# Prosthesis_Motor_Shield.net
KiCad netlist of a schematic drawn in EAGLE
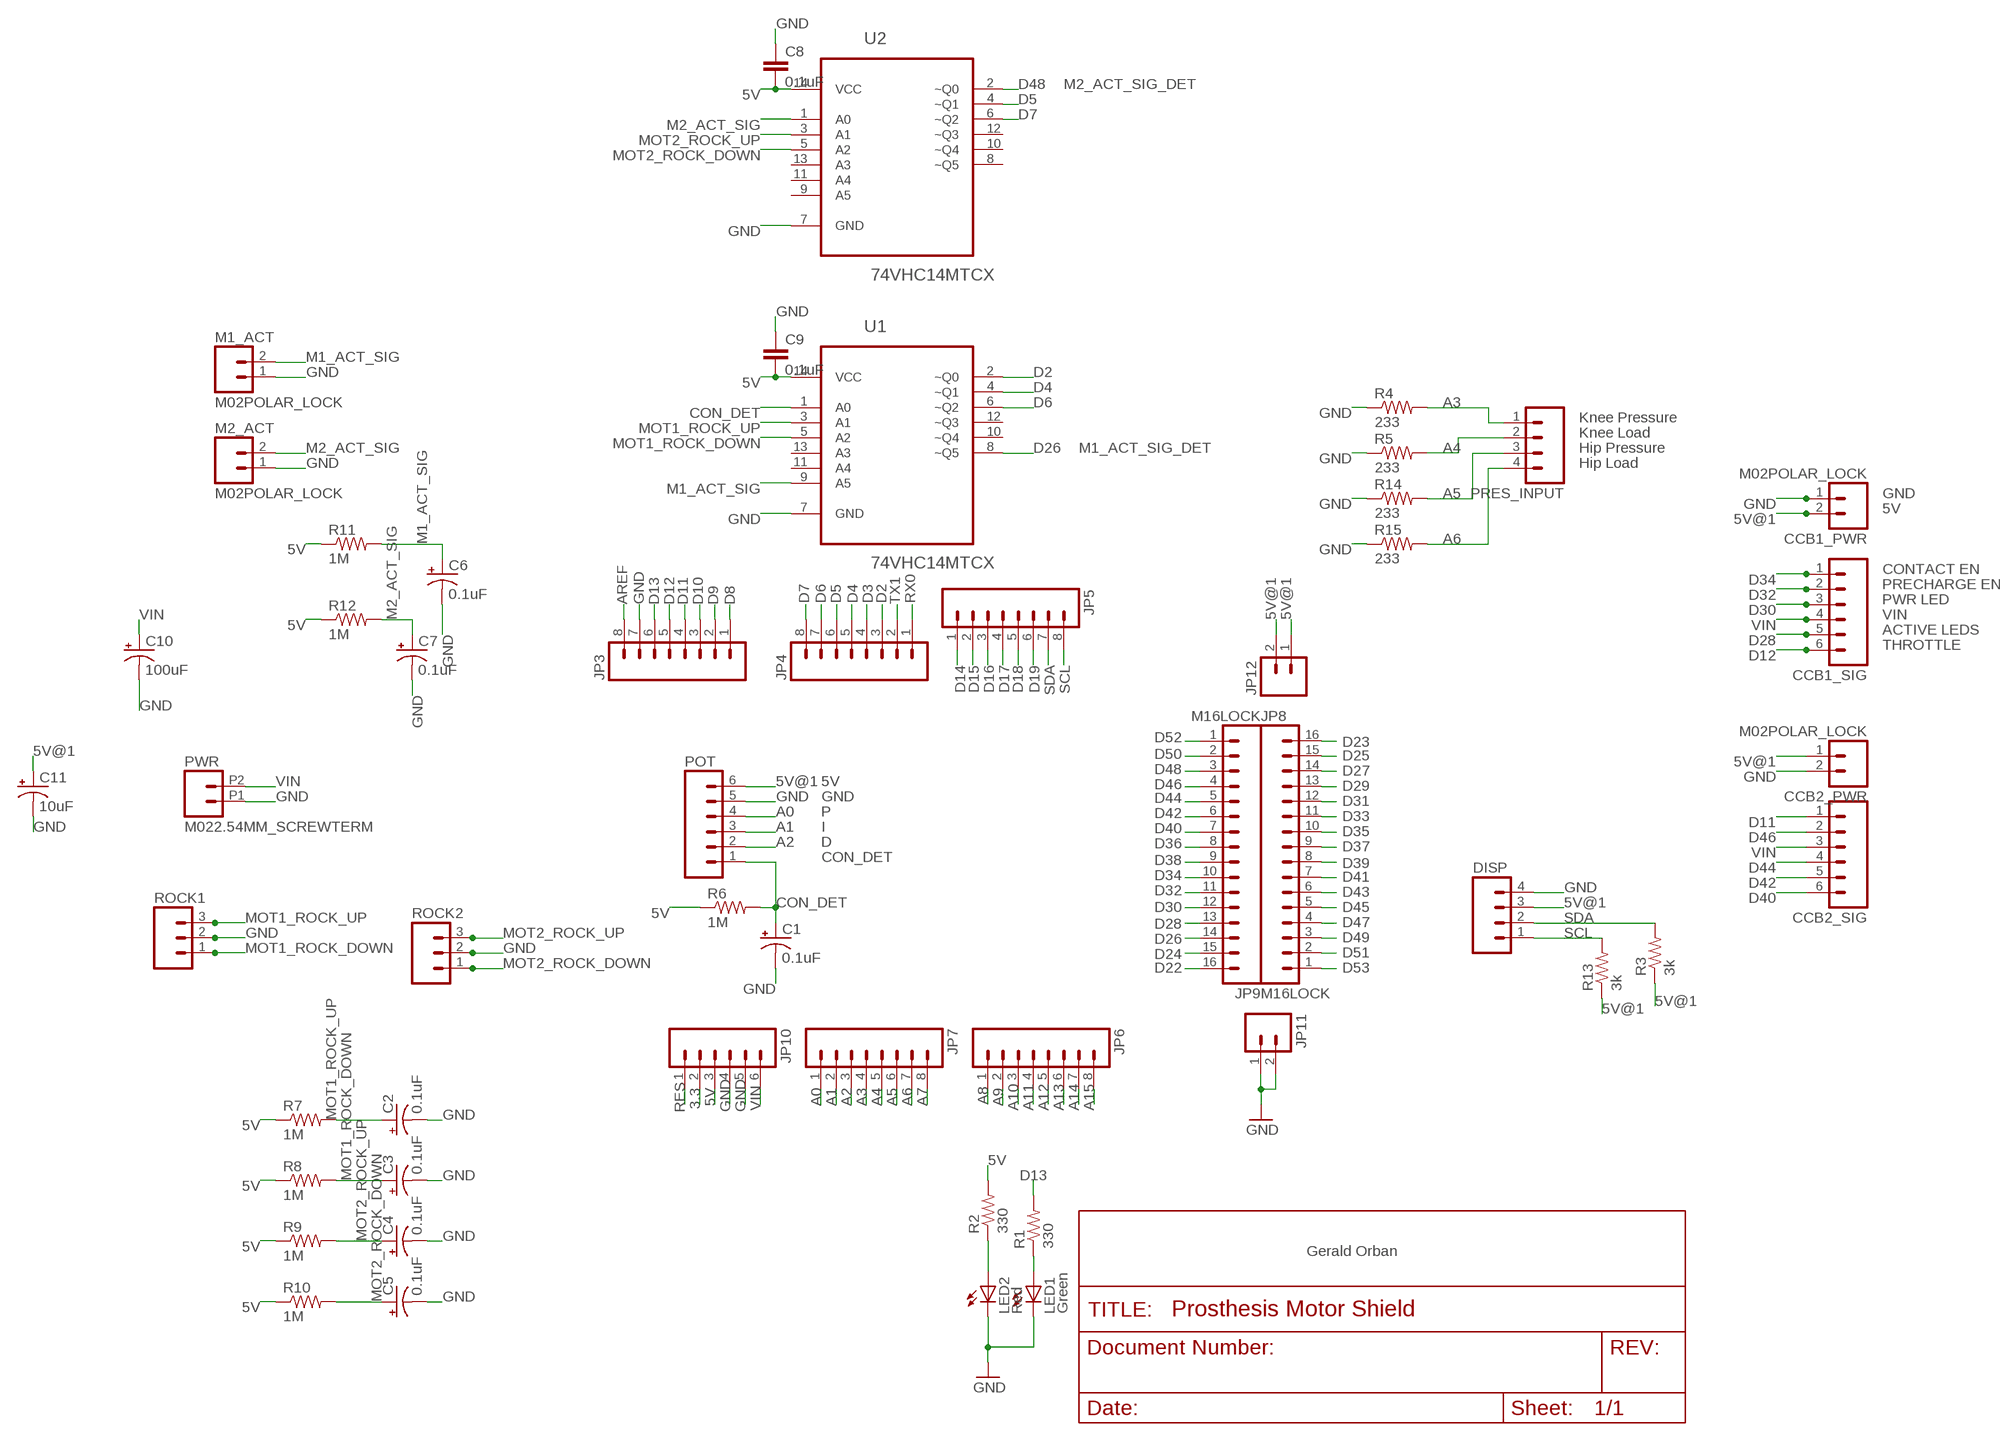
[diagram p0: schematic, sheet 1]

(export (version "E")
  (design (tool "Eeschema 10.0.6"))
  (components
    (comp (ref "C1")
      (value "0.1uF")
      (footprint "eagle-import:EIA3216")
      (libsource (lib "eagle-import") (part "CAP_POL1206"))
    )
    (comp (ref "C2")
      (value "0.1uF")
      (footprint "eagle-import:EIA3216")
      (libsource (lib "eagle-import") (part "CAP_POL1206"))
    )
    (comp (ref "C3")
      (value "0.1uF")
      (footprint "eagle-import:EIA3216")
      (libsource (lib "eagle-import") (part "CAP_POL1206"))
    )
    (comp (ref "C4")
      (value "0.1uF")
      (footprint "eagle-import:EIA3216")
      (libsource (lib "eagle-import") (part "CAP_POL1206"))
    )
    (comp (ref "C5")
      (value "0.1uF")
      (footprint "eagle-import:EIA3216")
      (libsource (lib "eagle-import") (part "CAP_POL1206"))
    )
    (comp (ref "C6")
      (value "0.1uF")
      (footprint "eagle-import:EIA3216")
      (libsource (lib "eagle-import") (part "CAP_POL1206"))
    )
    (comp (ref "C7")
      (value "0.1uF")
      (footprint "eagle-import:EIA3216")
      (libsource (lib "eagle-import") (part "CAP_POL1206"))
    )
    (comp (ref "C8")
      (value "0.1uF")
      (footprint "eagle-import:0603-CAP")
      (libsource (lib "eagle-import") (part "CAP0603-CAP"))
    )
    (comp (ref "C9")
      (value "0.1uF")
      (footprint "eagle-import:0603-CAP")
      (libsource (lib "eagle-import") (part "CAP0603-CAP"))
    )
    (comp (ref "C10")
      (value "100uF")
      (footprint "eagle-import:CPOL-RADIAL-100UF-25V")
      (libsource (lib "eagle-import") (part "CAP_POLPTH1"))
    )
    (comp (ref "C11")
      (value "10uF")
      (footprint "eagle-import:CPOL-RADIAL-10UF-25V")
      (libsource (lib "eagle-import") (part "CAP_POLPTH2"))
    )
    (comp (ref "CCB1_PWR")
      (value "M02POLAR_LOCK")
      (footprint "eagle-import:MOLEX-1X2_LOCK")
      (libsource (lib "eagle-import") (part "SparkFun-Connectors_M02POLAR_LOCK"))
    )
    (comp (ref "CCB1_SIG")
      (value "M06POLAR_LOCK")
      (footprint "eagle-import:MOLEX-1X6_LOCK")
      (libsource (lib "eagle-import") (part "SparkFun-Connectors_M06POLAR_LOCK"))
    )
    (comp (ref "CCB2_PWR")
      (value "M02POLAR_LOCK")
      (footprint "eagle-import:MOLEX-1X2_LOCK")
      (libsource (lib "eagle-import") (part "SparkFun-Connectors_M02POLAR_LOCK"))
    )
    (comp (ref "CCB2_SIG")
      (value "M06POLAR_LOCK")
      (footprint "eagle-import:MOLEX-1X6_LOCK")
      (libsource (lib "eagle-import") (part "SparkFun-Connectors_M06POLAR_LOCK"))
    )
    (comp (ref "DISP")
      (value "M04POLAR_LOCK")
      (footprint "eagle-import:MOLEX-1X4_LOCK")
      (libsource (lib "eagle-import") (part "M04POLAR_LOCK"))
    )
    (comp (ref "JP3")
      (value "M08LOCK")
      (footprint "eagle-import:1X08_LOCK")
      (libsource (lib "eagle-import") (part "M08LOCK"))
    )
    (comp (ref "JP4")
      (value "M08LOCK")
      (footprint "eagle-import:1X08_LOCK")
      (libsource (lib "eagle-import") (part "M08LOCK"))
    )
    (comp (ref "JP5")
      (value "M08LOCK")
      (footprint "eagle-import:1X08_LOCK")
      (libsource (lib "eagle-import") (part "M08LOCK"))
    )
    (comp (ref "JP6")
      (value "M08LOCK")
      (footprint "eagle-import:1X08_LOCK")
      (libsource (lib "eagle-import") (part "M08LOCK"))
    )
    (comp (ref "JP7")
      (value "M08LOCK")
      (footprint "eagle-import:1X08_LOCK")
      (libsource (lib "eagle-import") (part "M08LOCK"))
    )
    (comp (ref "JP8")
      (value "M16LOCK")
      (footprint "eagle-import:1X16_LOCK")
      (libsource (lib "eagle-import") (part "M16LOCK"))
    )
    (comp (ref "JP9")
      (value "M16LOCK")
      (footprint "eagle-import:1X16_LOCK")
      (libsource (lib "eagle-import") (part "M16LOCK"))
    )
    (comp (ref "JP10")
      (value "M06LOCK")
      (footprint "eagle-import:1X06_LOCK")
      (libsource (lib "eagle-import") (part "M06LOCK"))
    )
    (comp (ref "JP11")
      (value "M02LOCK")
      (footprint "eagle-import:1X02_LOCK")
      (libsource (lib "eagle-import") (part "M02LOCK"))
    )
    (comp (ref "JP12")
      (value "M02LOCK")
      (footprint "eagle-import:1X02_LOCK")
      (libsource (lib "eagle-import") (part "M02LOCK"))
    )
    (comp (ref "LED1")
      (value "Green")
      (footprint "eagle-import:LED-1206")
      (libsource (lib "eagle-import") (part "LED1206"))
    )
    (comp (ref "LED2")
      (value "Red")
      (footprint "eagle-import:LED-1206")
      (libsource (lib "eagle-import") (part "LED1206"))
    )
    (comp (ref "M1_ACT")
      (value "M02POLAR_LOCK")
      (footprint "eagle-import:MOLEX-1X2_LOCK")
      (libsource (lib "eagle-import") (part "SparkFun-Connectors_M02POLAR_LOCK"))
    )
    (comp (ref "M2_ACT")
      (value "M02POLAR_LOCK")
      (footprint "eagle-import:MOLEX-1X2_LOCK")
      (libsource (lib "eagle-import") (part "SparkFun-Connectors_M02POLAR_LOCK"))
    )
    (comp (ref "POT")
      (value "M06POLAR_LOCK")
      (footprint "eagle-import:MOLEX-1X6_LOCK")
      (libsource (lib "eagle-import") (part "SparkFun-Connectors_M06POLAR_LOCK"))
    )
    (comp (ref "PRES_INPUT")
      (value "M04POLAR_LOCK")
      (footprint "eagle-import:MOLEX-1X4_LOCK")
      (libsource (lib "eagle-import") (part "M04POLAR_LOCK"))
    )
    (comp (ref "PWR")
      (value "M022.54MM_SCREWTERM")
      (footprint "eagle-import:1X02_2.54_SCREWTERM")
      (libsource (lib "eagle-import") (part "M022.54MM_SCREWTERM"))
    )
    (comp (ref "R1")
      (value "330")
      (footprint "eagle-import:0805")
      (libsource (lib "eagle-import") (part "RESISTOR0805-RES"))
    )
    (comp (ref "R2")
      (value "330")
      (footprint "eagle-import:0805")
      (libsource (lib "eagle-import") (part "RESISTOR0805-RES"))
    )
    (comp (ref "R3")
      (value "3k")
      (footprint "eagle-import:0603-RES")
      (libsource (lib "eagle-import") (part "RESISTOR0603"))
    )
    (comp (ref "R4")
      (value "233")
      (footprint "eagle-import:AXIAL-0.4")
      (libsource (lib "eagle-import") (part "RESISTORPTH-1/4W"))
    )
    (comp (ref "R5")
      (value "233")
      (footprint "eagle-import:AXIAL-0.4")
      (libsource (lib "eagle-import") (part "RESISTORPTH-1/4W"))
    )
    (comp (ref "R6")
      (value "1M")
      (footprint "eagle-import:0603-RES")
      (libsource (lib "eagle-import") (part "RESISTOR0603-RES"))
    )
    (comp (ref "R7")
      (value "1M")
      (footprint "eagle-import:0603-RES")
      (libsource (lib "eagle-import") (part "RESISTOR0603"))
    )
    (comp (ref "R8")
      (value "1M")
      (footprint "eagle-import:0603-RES")
      (libsource (lib "eagle-import") (part "RESISTOR0603"))
    )
    (comp (ref "R9")
      (value "1M")
      (footprint "eagle-import:0603-RES")
      (libsource (lib "eagle-import") (part "RESISTOR0603"))
    )
    (comp (ref "R10")
      (value "1M")
      (footprint "eagle-import:0603-RES")
      (libsource (lib "eagle-import") (part "RESISTOR0603"))
    )
    (comp (ref "R11")
      (value "1M")
      (footprint "eagle-import:0603-RES")
      (libsource (lib "eagle-import") (part "RESISTOR0603"))
    )
    (comp (ref "R12")
      (value "1M")
      (footprint "eagle-import:0603-RES")
      (libsource (lib "eagle-import") (part "RESISTOR0603"))
    )
    (comp (ref "R13")
      (value "3k")
      (footprint "eagle-import:0603-RES")
      (libsource (lib "eagle-import") (part "RESISTOR0603"))
    )
    (comp (ref "R14")
      (value "233")
      (footprint "eagle-import:AXIAL-0.4")
      (libsource (lib "eagle-import") (part "RESISTORPTH-1/4W"))
    )
    (comp (ref "R15")
      (value "233")
      (footprint "eagle-import:AXIAL-0.4")
      (libsource (lib "eagle-import") (part "RESISTORPTH-1/4W"))
    )
    (comp (ref "ROCK1")
      (value "M03POLAR_LOCK")
      (footprint "eagle-import:MOLEX-1X3_LOCK")
      (libsource (lib "eagle-import") (part "M03POLAR_LOCK"))
    )
    (comp (ref "ROCK2")
      (value "M03POLAR_LOCK")
      (footprint "eagle-import:MOLEX-1X3_LOCK")
      (libsource (lib "eagle-import") (part "M03POLAR_LOCK"))
    )
    (comp (ref "U1")
      (value "74VHC14MTCX")
      (footprint "eagle-import:SOP65P640X120-14N")
      (libsource (lib "eagle-import") (part "74VHC14MTCX"))
    )
    (comp (ref "U2")
      (value "74VHC14MTCX")
      (footprint "eagle-import:SOP65P640X120-14N")
      (libsource (lib "eagle-import") (part "74VHC14MTCX"))
    )
  )
  (nets
    (net (code "1") (name "/3.3") (class "Default")
      (node (ref "JP10") (pin "2") (pinfunction "2_2") (pintype "passive"))
    )
    (net (code "2") (name "/5V") (class "Default")
      (node (ref "C8") (pin "2") (pinfunction "2_2") (pintype "passive"))
      (node (ref "C9") (pin "2") (pinfunction "2_2") (pintype "passive"))
      (node (ref "JP10") (pin "3") (pinfunction "3_3") (pintype "passive"))
      (node (ref "R10") (pin "1") (pinfunction "1_1") (pintype "passive"))
      (node (ref "R11") (pin "1") (pinfunction "1_1") (pintype "passive"))
      (node (ref "R12") (pin "1") (pinfunction "1_1") (pintype "passive"))
      (node (ref "R2") (pin "2") (pinfunction "2_2") (pintype "passive"))
      (node (ref "R6") (pin "1") (pinfunction "1_1") (pintype "passive"))
      (node (ref "R7") (pin "1") (pinfunction "1_1") (pintype "passive"))
      (node (ref "R8") (pin "1") (pinfunction "1_1") (pintype "passive"))
      (node (ref "R9") (pin "1") (pinfunction "1_1") (pintype "passive"))
      (node (ref "U1") (pin "14") (pinfunction "VCC_14") (pintype "power_in"))
      (node (ref "U2") (pin "14") (pinfunction "VCC_14") (pintype "power_in"))
    )
    (net (code "3") (name "/5V@1") (class "Default")
      (node (ref "C11") (pin "1") (pinfunction "+_1") (pintype "passive"))
      (node (ref "CCB1_PWR") (pin "2") (pinfunction "2_2") (pintype "passive"))
      (node (ref "CCB2_PWR") (pin "1") (pinfunction "1_1") (pintype "passive"))
      (node (ref "DISP") (pin "3") (pinfunction "3_3") (pintype "passive"))
      (node (ref "JP12") (pin "1") (pinfunction "1_1") (pintype "passive"))
      (node (ref "JP12") (pin "2") (pinfunction "2_2") (pintype "passive"))
      (node (ref "POT") (pin "6") (pinfunction "6_6") (pintype "passive"))
      (node (ref "R13") (pin "1") (pinfunction "1_1") (pintype "passive"))
      (node (ref "R3") (pin "1") (pinfunction "1_1") (pintype "passive"))
    )
    (net (code "4") (name "/A0") (class "Default")
      (node (ref "JP7") (pin "1") (pinfunction "1_1") (pintype "passive"))
      (node (ref "POT") (pin "4") (pinfunction "4_4") (pintype "passive"))
    )
    (net (code "5") (name "/A1") (class "Default")
      (node (ref "JP7") (pin "2") (pinfunction "2_2") (pintype "passive"))
      (node (ref "POT") (pin "3") (pinfunction "3_3") (pintype "passive"))
    )
    (net (code "6") (name "/A2") (class "Default")
      (node (ref "JP7") (pin "3") (pinfunction "3_3") (pintype "passive"))
      (node (ref "POT") (pin "2") (pinfunction "2_2") (pintype "passive"))
    )
    (net (code "7") (name "/A3") (class "Default")
      (node (ref "JP7") (pin "4") (pinfunction "4_4") (pintype "passive"))
      (node (ref "PRES_INPUT") (pin "1") (pinfunction "1_1") (pintype "passive"))
      (node (ref "R4") (pin "P$2") (pinfunction "2_P$2") (pintype "passive"))
    )
    (net (code "8") (name "/A4") (class "Default")
      (node (ref "JP7") (pin "5") (pinfunction "5_5") (pintype "passive"))
      (node (ref "PRES_INPUT") (pin "2") (pinfunction "2_2") (pintype "passive"))
      (node (ref "R5") (pin "P$2") (pinfunction "2_P$2") (pintype "passive"))
    )
    (net (code "9") (name "/A5") (class "Default")
      (node (ref "JP7") (pin "6") (pinfunction "6_6") (pintype "passive"))
      (node (ref "PRES_INPUT") (pin "3") (pinfunction "3_3") (pintype "passive"))
      (node (ref "R14") (pin "P$2") (pinfunction "2_P$2") (pintype "passive"))
    )
    (net (code "10") (name "/A6") (class "Default")
      (node (ref "JP7") (pin "7") (pinfunction "7_7") (pintype "passive"))
      (node (ref "PRES_INPUT") (pin "4") (pinfunction "4_4") (pintype "passive"))
      (node (ref "R15") (pin "P$2") (pinfunction "2_P$2") (pintype "passive"))
    )
    (net (code "11") (name "/A7") (class "Default")
      (node (ref "JP7") (pin "8") (pinfunction "8_8") (pintype "passive"))
    )
    (net (code "12") (name "/A8") (class "Default")
      (node (ref "JP6") (pin "1") (pinfunction "1_1") (pintype "passive"))
    )
    (net (code "13") (name "/A9") (class "Default")
      (node (ref "JP6") (pin "2") (pinfunction "2_2") (pintype "passive"))
    )
    (net (code "14") (name "/A10") (class "Default")
      (node (ref "JP6") (pin "3") (pinfunction "3_3") (pintype "passive"))
    )
    (net (code "15") (name "/A11") (class "Default")
      (node (ref "JP6") (pin "4") (pinfunction "4_4") (pintype "passive"))
    )
    (net (code "16") (name "/A12") (class "Default")
      (node (ref "JP6") (pin "5") (pinfunction "5_5") (pintype "passive"))
    )
    (net (code "17") (name "/A13") (class "Default")
      (node (ref "JP6") (pin "6") (pinfunction "6_6") (pintype "passive"))
    )
    (net (code "18") (name "/A14") (class "Default")
      (node (ref "JP6") (pin "7") (pinfunction "7_7") (pintype "passive"))
    )
    (net (code "19") (name "/A15") (class "Default")
      (node (ref "JP6") (pin "8") (pinfunction "8_8") (pintype "passive"))
    )
    (net (code "20") (name "/AREF") (class "Default")
      (node (ref "JP3") (pin "8") (pinfunction "8_8") (pintype "passive"))
    )
    (net (code "21") (name "/CON_DET") (class "Default")
      (node (ref "C1") (pin "A") (pinfunction "+_A") (pintype "passive"))
      (node (ref "POT") (pin "1") (pinfunction "1_1") (pintype "passive"))
      (node (ref "R6") (pin "2") (pinfunction "2_2") (pintype "passive"))
      (node (ref "U1") (pin "1") (pinfunction "A0_1") (pintype "input"))
    )
    (net (code "22") (name "/D2") (class "Default")
      (node (ref "JP4") (pin "3") (pinfunction "3_3") (pintype "passive"))
      (node (ref "U1") (pin "2") (pinfunction "~{Q0}_2") (pintype "output"))
    )
    (net (code "23") (name "/D3") (class "Default")
      (node (ref "JP4") (pin "4") (pinfunction "4_4") (pintype "passive"))
    )
    (net (code "24") (name "/D4") (class "Default")
      (node (ref "JP4") (pin "5") (pinfunction "5_5") (pintype "passive"))
      (node (ref "U1") (pin "4") (pinfunction "~{Q1}_4") (pintype "output"))
    )
    (net (code "25") (name "/D5") (class "Default")
      (node (ref "JP4") (pin "6") (pinfunction "6_6") (pintype "passive"))
      (node (ref "U2") (pin "4") (pinfunction "~{Q1}_4") (pintype "output"))
    )
    (net (code "26") (name "/D6") (class "Default")
      (node (ref "JP4") (pin "7") (pinfunction "7_7") (pintype "passive"))
      (node (ref "U1") (pin "6") (pinfunction "~{Q2}_6") (pintype "output"))
    )
    (net (code "27") (name "/D7") (class "Default")
      (node (ref "JP4") (pin "8") (pinfunction "8_8") (pintype "passive"))
      (node (ref "U2") (pin "6") (pinfunction "~{Q2}_6") (pintype "output"))
    )
    (net (code "28") (name "/D8") (class "Default")
      (node (ref "JP3") (pin "1") (pinfunction "1_1") (pintype "passive"))
    )
    (net (code "29") (name "/D9") (class "Default")
      (node (ref "JP3") (pin "2") (pinfunction "2_2") (pintype "passive"))
    )
    (net (code "30") (name "/D10") (class "Default")
      (node (ref "JP3") (pin "3") (pinfunction "3_3") (pintype "passive"))
    )
    (net (code "31") (name "/D11") (class "Default")
      (node (ref "CCB2_SIG") (pin "1") (pinfunction "1_1") (pintype "passive"))
      (node (ref "JP3") (pin "4") (pinfunction "4_4") (pintype "passive"))
    )
    (net (code "32") (name "/D12") (class "Default")
      (node (ref "CCB1_SIG") (pin "6") (pinfunction "6_6") (pintype "passive"))
      (node (ref "JP3") (pin "5") (pinfunction "5_5") (pintype "passive"))
    )
    (net (code "33") (name "/D13") (class "Default")
      (node (ref "JP3") (pin "6") (pinfunction "6_6") (pintype "passive"))
      (node (ref "R1") (pin "2") (pinfunction "2_2") (pintype "passive"))
    )
    (net (code "34") (name "/D14") (class "Default")
      (node (ref "JP5") (pin "1") (pinfunction "1_1") (pintype "passive"))
    )
    (net (code "35") (name "/D15") (class "Default")
      (node (ref "JP5") (pin "2") (pinfunction "2_2") (pintype "passive"))
    )
    (net (code "36") (name "/D16") (class "Default")
      (node (ref "JP5") (pin "3") (pinfunction "3_3") (pintype "passive"))
    )
    (net (code "37") (name "/D17") (class "Default")
      (node (ref "JP5") (pin "4") (pinfunction "4_4") (pintype "passive"))
    )
    (net (code "38") (name "/D18") (class "Default")
      (node (ref "JP5") (pin "5") (pinfunction "5_5") (pintype "passive"))
    )
    (net (code "39") (name "/D19") (class "Default")
      (node (ref "JP5") (pin "6") (pinfunction "6_6") (pintype "passive"))
    )
    (net (code "40") (name "/D22") (class "Default")
      (node (ref "JP9") (pin "16") (pinfunction "16_16") (pintype "passive"))
    )
    (net (code "41") (name "/D23") (class "Default")
      (node (ref "JP8") (pin "16") (pinfunction "16_16") (pintype "passive"))
    )
    (net (code "42") (name "/D24") (class "Default")
      (node (ref "JP9") (pin "15") (pinfunction "15_15") (pintype "passive"))
    )
    (net (code "43") (name "/D25") (class "Default")
      (node (ref "JP8") (pin "15") (pinfunction "15_15") (pintype "passive"))
    )
    (net (code "44") (name "/D26") (class "Default")
      (node (ref "JP9") (pin "14") (pinfunction "14_14") (pintype "passive"))
      (node (ref "U1") (pin "8") (pinfunction "~{Q5}_8") (pintype "output"))
    )
    (net (code "45") (name "/D27") (class "Default")
      (node (ref "JP8") (pin "14") (pinfunction "14_14") (pintype "passive"))
    )
    (net (code "46") (name "/D28") (class "Default")
      (node (ref "CCB1_SIG") (pin "5") (pinfunction "5_5") (pintype "passive"))
      (node (ref "JP9") (pin "13") (pinfunction "13_13") (pintype "passive"))
    )
    (net (code "47") (name "/D29") (class "Default")
      (node (ref "JP8") (pin "13") (pinfunction "13_13") (pintype "passive"))
    )
    (net (code "48") (name "/D30") (class "Default")
      (node (ref "CCB1_SIG") (pin "3") (pinfunction "3_3") (pintype "passive"))
      (node (ref "JP9") (pin "12") (pinfunction "12_12") (pintype "passive"))
    )
    (net (code "49") (name "/D31") (class "Default")
      (node (ref "JP8") (pin "12") (pinfunction "12_12") (pintype "passive"))
    )
    (net (code "50") (name "/D32") (class "Default")
      (node (ref "CCB1_SIG") (pin "2") (pinfunction "2_2") (pintype "passive"))
      (node (ref "JP9") (pin "11") (pinfunction "11_11") (pintype "passive"))
    )
    (net (code "51") (name "/D33") (class "Default")
      (node (ref "JP8") (pin "11") (pinfunction "11_11") (pintype "passive"))
    )
    (net (code "52") (name "/D34") (class "Default")
      (node (ref "CCB1_SIG") (pin "1") (pinfunction "1_1") (pintype "passive"))
      (node (ref "JP9") (pin "10") (pinfunction "10_10") (pintype "passive"))
    )
    (net (code "53") (name "/D35") (class "Default")
      (node (ref "JP8") (pin "10") (pinfunction "10_10") (pintype "passive"))
    )
    (net (code "54") (name "/D36") (class "Default")
      (node (ref "JP9") (pin "9") (pinfunction "9_9") (pintype "passive"))
    )
    (net (code "55") (name "/D37") (class "Default")
      (node (ref "JP8") (pin "9") (pinfunction "9_9") (pintype "passive"))
    )
    (net (code "56") (name "/D38") (class "Default")
      (node (ref "JP9") (pin "8") (pinfunction "8_8") (pintype "passive"))
    )
    (net (code "57") (name "/D39") (class "Default")
      (node (ref "JP8") (pin "8") (pinfunction "8_8") (pintype "passive"))
    )
    (net (code "58") (name "/D40") (class "Default")
      (node (ref "CCB2_SIG") (pin "6") (pinfunction "6_6") (pintype "passive"))
      (node (ref "JP9") (pin "7") (pinfunction "7_7") (pintype "passive"))
    )
    (net (code "59") (name "/D41") (class "Default")
      (node (ref "JP8") (pin "7") (pinfunction "7_7") (pintype "passive"))
    )
    (net (code "60") (name "/D42") (class "Default")
      (node (ref "CCB2_SIG") (pin "5") (pinfunction "5_5") (pintype "passive"))
      (node (ref "JP9") (pin "6") (pinfunction "6_6") (pintype "passive"))
    )
    (net (code "61") (name "/D43") (class "Default")
      (node (ref "JP8") (pin "6") (pinfunction "6_6") (pintype "passive"))
    )
    (net (code "62") (name "/D44") (class "Default")
      (node (ref "CCB2_SIG") (pin "4") (pinfunction "4_4") (pintype "passive"))
      (node (ref "JP9") (pin "5") (pinfunction "5_5") (pintype "passive"))
    )
    (net (code "63") (name "/D45") (class "Default")
      (node (ref "JP8") (pin "5") (pinfunction "5_5") (pintype "passive"))
    )
    (net (code "64") (name "/D46") (class "Default")
      (node (ref "CCB2_SIG") (pin "2") (pinfunction "2_2") (pintype "passive"))
      (node (ref "JP9") (pin "4") (pinfunction "4_4") (pintype "passive"))
    )
    (net (code "65") (name "/D47") (class "Default")
      (node (ref "JP8") (pin "4") (pinfunction "4_4") (pintype "passive"))
    )
    (net (code "66") (name "/D48") (class "Default")
      (node (ref "JP9") (pin "3") (pinfunction "3_3") (pintype "passive"))
      (node (ref "U2") (pin "2") (pinfunction "~{Q0}_2") (pintype "output"))
    )
    (net (code "67") (name "/D49") (class "Default")
      (node (ref "JP8") (pin "3") (pinfunction "3_3") (pintype "passive"))
    )
    (net (code "68") (name "/D50") (class "Default")
      (node (ref "JP9") (pin "2") (pinfunction "2_2") (pintype "passive"))
    )
    (net (code "69") (name "/D51") (class "Default")
      (node (ref "JP8") (pin "2") (pinfunction "2_2") (pintype "passive"))
    )
    (net (code "70") (name "/D52") (class "Default")
      (node (ref "JP9") (pin "1") (pinfunction "1_1") (pintype "passive"))
    )
    (net (code "71") (name "/D53") (class "Default")
      (node (ref "JP8") (pin "1") (pinfunction "1_1") (pintype "passive"))
    )
    (net (code "72") (name "/M1_ACT_SIG") (class "Default")
      (node (ref "C6") (pin "A") (pinfunction "+_A") (pintype "passive"))
      (node (ref "M1_ACT") (pin "2") (pinfunction "2_2") (pintype "passive"))
      (node (ref "R11") (pin "2") (pinfunction "2_2") (pintype "passive"))
      (node (ref "U1") (pin "9") (pinfunction "A5_9") (pintype "input"))
    )
    (net (code "73") (name "/M2_ACT_SIG") (class "Default")
      (node (ref "C7") (pin "A") (pinfunction "+_A") (pintype "passive"))
      (node (ref "M2_ACT") (pin "2") (pinfunction "2_2") (pintype "passive"))
      (node (ref "R12") (pin "2") (pinfunction "2_2") (pintype "passive"))
      (node (ref "U2") (pin "1") (pinfunction "A0_1") (pintype "input"))
    )
    (net (code "74") (name "/MOT1_ROCK_DOWN") (class "Default")
      (node (ref "C3") (pin "A") (pinfunction "+_A") (pintype "passive"))
      (node (ref "R8") (pin "2") (pinfunction "2_2") (pintype "passive"))
      (node (ref "ROCK1") (pin "1") (pinfunction "1_1") (pintype "passive"))
      (node (ref "U1") (pin "5") (pinfunction "A2_5") (pintype "input"))
    )
    (net (code "75") (name "/MOT1_ROCK_UP") (class "Default")
      (node (ref "C2") (pin "A") (pinfunction "+_A") (pintype "passive"))
      (node (ref "R7") (pin "2") (pinfunction "2_2") (pintype "passive"))
      (node (ref "ROCK1") (pin "3") (pinfunction "3_3") (pintype "passive"))
      (node (ref "U1") (pin "3") (pinfunction "A1_3") (pintype "input"))
    )
    (net (code "76") (name "/MOT2_ROCK_DOWN") (class "Default")
      (node (ref "C5") (pin "A") (pinfunction "+_A") (pintype "passive"))
      (node (ref "R10") (pin "2") (pinfunction "2_2") (pintype "passive"))
      (node (ref "ROCK2") (pin "1") (pinfunction "1_1") (pintype "passive"))
      (node (ref "U2") (pin "5") (pinfunction "A2_5") (pintype "input"))
    )
    (net (code "77") (name "/MOT2_ROCK_UP") (class "Default")
      (node (ref "C4") (pin "A") (pinfunction "+_A") (pintype "passive"))
      (node (ref "R9") (pin "2") (pinfunction "2_2") (pintype "passive"))
      (node (ref "ROCK2") (pin "3") (pinfunction "3_3") (pintype "passive"))
      (node (ref "U2") (pin "3") (pinfunction "A1_3") (pintype "input"))
    )
    (net (code "78") (name "/RES") (class "Default")
      (node (ref "JP10") (pin "1") (pinfunction "1_1") (pintype "passive"))
    )
    (net (code "79") (name "/RX0") (class "Default")
      (node (ref "JP4") (pin "1") (pinfunction "1_1") (pintype "passive"))
    )
    (net (code "80") (name "/SCL") (class "Default")
      (node (ref "DISP") (pin "1") (pinfunction "1_1") (pintype "passive"))
      (node (ref "JP5") (pin "8") (pinfunction "8_8") (pintype "passive"))
      (node (ref "R13") (pin "2") (pinfunction "2_2") (pintype "passive"))
    )
    (net (code "81") (name "/SDA") (class "Default")
      (node (ref "DISP") (pin "2") (pinfunction "2_2") (pintype "passive"))
      (node (ref "JP5") (pin "7") (pinfunction "7_7") (pintype "passive"))
      (node (ref "R3") (pin "2") (pinfunction "2_2") (pintype "passive"))
    )
    (net (code "82") (name "/TX1") (class "Default")
      (node (ref "JP4") (pin "2") (pinfunction "2_2") (pintype "passive"))
    )
    (net (code "83") (name "/VIN") (class "Default")
      (node (ref "C10") (pin "1") (pinfunction "+_1") (pintype "passive"))
      (node (ref "CCB1_SIG") (pin "4") (pinfunction "4_4") (pintype "passive"))
      (node (ref "CCB2_SIG") (pin "3") (pinfunction "3_3") (pintype "passive"))
      (node (ref "JP10") (pin "6") (pinfunction "6_6") (pintype "passive"))
      (node (ref "PWR") (pin "P2") (pinfunction "2_P2") (pintype "passive"))
    )
    (net (code "84") (name "GND") (class "Default")
      (node (ref "C1") (pin "C") (pinfunction "-_C") (pintype "passive"))
      (node (ref "C10") (pin "2") (pinfunction "-_2") (pintype "passive"))
      (node (ref "C11") (pin "2") (pinfunction "-_2") (pintype "passive"))
      (node (ref "C2") (pin "C") (pinfunction "-_C") (pintype "passive"))
      (node (ref "C3") (pin "C") (pinfunction "-_C") (pintype "passive"))
      (node (ref "C4") (pin "C") (pinfunction "-_C") (pintype "passive"))
      (node (ref "C5") (pin "C") (pinfunction "-_C") (pintype "passive"))
      (node (ref "C6") (pin "C") (pinfunction "-_C") (pintype "passive"))
      (node (ref "C7") (pin "C") (pinfunction "-_C") (pintype "passive"))
      (node (ref "C8") (pin "1") (pinfunction "1_1") (pintype "passive"))
      (node (ref "C9") (pin "1") (pinfunction "1_1") (pintype "passive"))
      (node (ref "CCB1_PWR") (pin "1") (pinfunction "1_1") (pintype "passive"))
      (node (ref "CCB2_PWR") (pin "2") (pinfunction "2_2") (pintype "passive"))
      (node (ref "DISP") (pin "4") (pinfunction "4_4") (pintype "passive"))
      (node (ref "JP10") (pin "4") (pinfunction "4_4") (pintype "passive"))
      (node (ref "JP10") (pin "5") (pinfunction "5_5") (pintype "passive"))
      (node (ref "JP11") (pin "1") (pinfunction "1_1") (pintype "passive"))
      (node (ref "JP11") (pin "2") (pinfunction "2_2") (pintype "passive"))
      (node (ref "JP3") (pin "7") (pinfunction "7_7") (pintype "passive"))
      (node (ref "LED1") (pin "C") (pinfunction "C_C") (pintype "passive"))
      (node (ref "LED2") (pin "C") (pinfunction "C_C") (pintype "passive"))
      (node (ref "M1_ACT") (pin "1") (pinfunction "1_1") (pintype "passive"))
      (node (ref "M2_ACT") (pin "1") (pinfunction "1_1") (pintype "passive"))
      (node (ref "POT") (pin "5") (pinfunction "5_5") (pintype "passive"))
      (node (ref "PWR") (pin "P1") (pinfunction "1_P1") (pintype "passive"))
      (node (ref "R14") (pin "P$1") (pinfunction "1_P$1") (pintype "passive"))
      (node (ref "R15") (pin "P$1") (pinfunction "1_P$1") (pintype "passive"))
      (node (ref "R4") (pin "P$1") (pinfunction "1_P$1") (pintype "passive"))
      (node (ref "R5") (pin "P$1") (pinfunction "1_P$1") (pintype "passive"))
      (node (ref "ROCK1") (pin "2") (pinfunction "2_2") (pintype "passive"))
      (node (ref "ROCK2") (pin "2") (pinfunction "2_2") (pintype "passive"))
      (node (ref "U1") (pin "7") (pinfunction "GND_7") (pintype "passive"))
      (node (ref "U2") (pin "7") (pinfunction "GND_7") (pintype "passive"))
    )
    (net (code "85") (name "Net-(LED1-PadA)") (class "Default")
      (node (ref "LED1") (pin "A") (pinfunction "A_A") (pintype "passive"))
      (node (ref "R1") (pin "1") (pinfunction "1_1") (pintype "passive"))
    )
    (net (code "86") (name "Net-(LED2-PadA)") (class "Default")
      (node (ref "LED2") (pin "A") (pinfunction "A_A") (pintype "passive"))
      (node (ref "R2") (pin "1") (pinfunction "1_1") (pintype "passive"))
    )
    (net (code "87") (name "unconnected-(U1-A3-Pad13)") (class "Default")
      (node (ref "U1") (pin "13") (pinfunction "A3_13") (pintype "input"))
    )
    (net (code "88") (name "unconnected-(U1-A4-Pad11)") (class "Default")
      (node (ref "U1") (pin "11") (pinfunction "A4_11") (pintype "input"))
    )
    (net (code "89") (name "unconnected-(U1-~{Q3}-Pad12)") (class "Default")
      (node (ref "U1") (pin "12") (pinfunction "~{Q3}_12") (pintype "output"))
    )
    (net (code "90") (name "unconnected-(U1-~{Q4}-Pad10)") (class "Default")
      (node (ref "U1") (pin "10") (pinfunction "~{Q4}_10") (pintype "output"))
    )
    (net (code "91") (name "unconnected-(U2-A3-Pad13)") (class "Default")
      (node (ref "U2") (pin "13") (pinfunction "A3_13") (pintype "input"))
    )
    (net (code "92") (name "unconnected-(U2-A4-Pad11)") (class "Default")
      (node (ref "U2") (pin "11") (pinfunction "A4_11") (pintype "input"))
    )
    (net (code "93") (name "unconnected-(U2-A5-Pad9)") (class "Default")
      (node (ref "U2") (pin "9") (pinfunction "A5_9") (pintype "input"))
    )
    (net (code "94") (name "unconnected-(U2-~{Q3}-Pad12)") (class "Default")
      (node (ref "U2") (pin "12") (pinfunction "~{Q3}_12") (pintype "output"))
    )
    (net (code "95") (name "unconnected-(U2-~{Q4}-Pad10)") (class "Default")
      (node (ref "U2") (pin "10") (pinfunction "~{Q4}_10") (pintype "output"))
    )
    (net (code "96") (name "unconnected-(U2-~{Q5}-Pad8)") (class "Default")
      (node (ref "U2") (pin "8") (pinfunction "~{Q5}_8") (pintype "output"))
    )
  )
)
